# Thermokoppel.net
KiCad netlist of a schematic drawn in Altium Designer
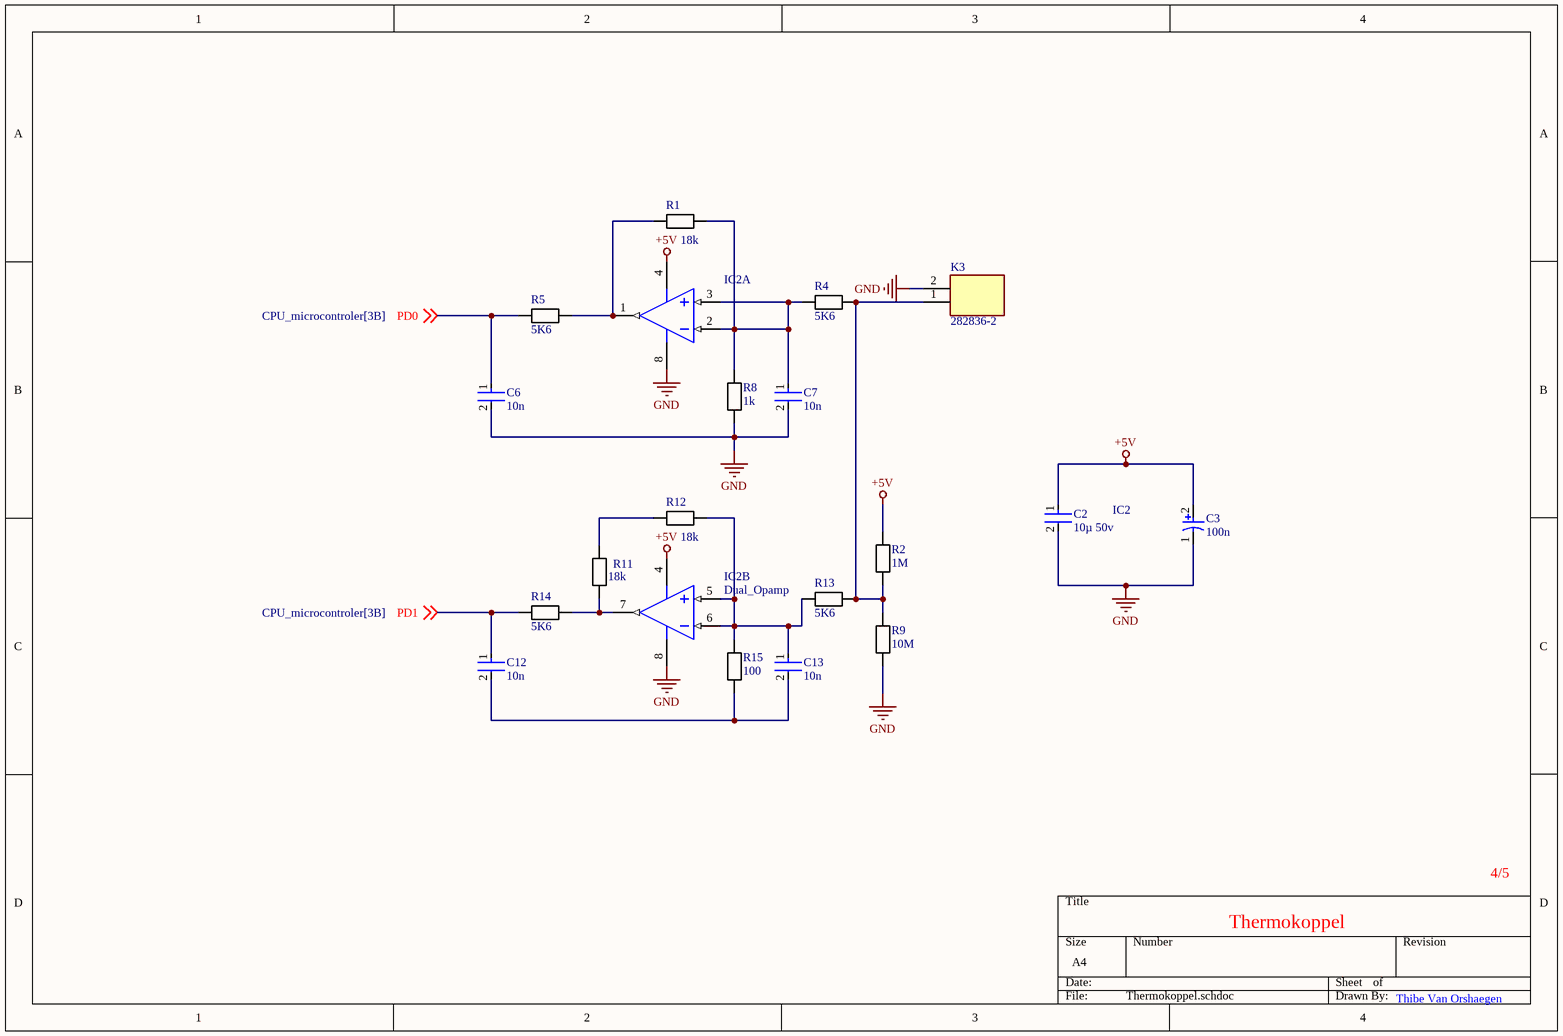
[diagram p0: Thermokoppel.schdoc]

(export (version "E")
  (design (tool "Eeschema 10.0.6"))
  (components
    (comp (ref "C2")
      (value "10µ 50v")
      (footprint "CC_0805_m")
      (fields
        (field (name "MANUFACTURER") "KEMET")
        (field (name "OCTOPART") "https://octopart.com/c0805c224k5ractu-kemet-144670")
        (field (name "MANUFACTURER PART NUMBER") "C0805C224K5RACTU")
      )
      (libsource (lib "Soldeerstation") (part "Capacitor_Ceramic"))
    )
    (comp (ref "C3")
      (value "100n")
      (footprint "CE_D8_L10")
      (fields (field (name "MANUFACTURER") "Panasonic"))
      (libsource (lib "Soldeerstation") (part "Capacitor_Electrolytic"))
    )
    (comp (ref "C6")
      (value "10n")
      (footprint "CC_0805_m")
      (fields
        (field (name "MANUFACTURER") "KEMET")
        (field (name "OCTOPART") "https://octopart.com/c0805c224k5ractu-kemet-144670")
        (field (name "MANUFACTURER PART NUMBER") "C0805C224K5RACTU")
      )
      (libsource (lib "Soldeerstation") (part "Capacitor_Ceramic"))
    )
    (comp (ref "C7")
      (value "10n")
      (footprint "CC_0805_m")
      (fields
        (field (name "MANUFACTURER") "KEMET")
        (field (name "OCTOPART") "https://octopart.com/c0805c224k5ractu-kemet-144670")
        (field (name "MANUFACTURER PART NUMBER") "C0805C224K5RACTU")
      )
      (libsource (lib "Soldeerstation") (part "Capacitor_Ceramic"))
    )
    (comp (ref "C12")
      (value "10n")
      (footprint "CC_0805_m")
      (fields
        (field (name "MANUFACTURER") "KEMET")
        (field (name "OCTOPART") "https://octopart.com/c0805c224k5ractu-kemet-144670")
        (field (name "MANUFACTURER PART NUMBER") "C0805C224K5RACTU")
      )
      (libsource (lib "Soldeerstation") (part "Capacitor_Ceramic"))
    )
    (comp (ref "C13")
      (value "10n")
      (footprint "CC_0805_m")
      (fields
        (field (name "MANUFACTURER") "KEMET")
        (field (name "OCTOPART") "https://octopart.com/c0805c224k5ractu-kemet-144670")
        (field (name "MANUFACTURER PART NUMBER") "C0805C224K5RACTU")
      )
      (libsource (lib "Soldeerstation") (part "Capacitor_Ceramic"))
    )
    (comp (ref "IC2")
      (value "Dual_Opamp")
      (footprint "MSOP_8_M")
      (libsource (lib "Schlib2") (part "Dual_Opamp"))
    )
    (comp (ref "K3")
      (value "282836-2")
      (footprint "PcbLib3:Schroefconnector 2 Pin")
      (description "Connector")
      (libsource (lib "Soldeerstation") (part "Schroefconnector 2 Pin L"))
    )
    (comp (ref "R1")
      (value "18k")
      (footprint "RESC2013X50X30ML20T20")
      (fields (field (name "MANUFACTURER") "Vishay Dale") (field (name "PART NUMBER") "CRCW08050000Z0EA"))
      (libsource (lib "Soldeerstation") (part "Weerstand"))
    )
    (comp (ref "R2")
      (value "1M")
      (footprint "RESC2013X50X30ML20T20")
      (fields (field (name "MANUFACTURER") "Vishay Dale") (field (name "PART NUMBER") "CRCW08050000Z0EA"))
      (libsource (lib "Soldeerstation") (part "Weerstand"))
    )
    (comp (ref "R4")
      (value "5K6")
      (footprint "RESC2013X50X30ML20T20")
      (fields (field (name "MANUFACTURER") "Vishay Dale") (field (name "PART NUMBER") "CRCW08050000Z0EA"))
      (libsource (lib "Soldeerstation") (part "Weerstand"))
    )
    (comp (ref "R5")
      (value "5K6")
      (footprint "RESC2013X50X30ML20T20")
      (fields (field (name "MANUFACTURER") "Vishay Dale") (field (name "PART NUMBER") "CRCW08050000Z0EA"))
      (libsource (lib "Soldeerstation") (part "Weerstand"))
    )
    (comp (ref "R8")
      (value "1k")
      (footprint "RESC2013X50X30ML20T20")
      (fields (field (name "MANUFACTURER") "Vishay Dale") (field (name "PART NUMBER") "CRCW08050000Z0EA"))
      (libsource (lib "Soldeerstation") (part "Weerstand"))
    )
    (comp (ref "R9")
      (value "10M")
      (footprint "RESC2013X50X30ML20T20")
      (fields (field (name "MANUFACTURER") "Vishay Dale") (field (name "PART NUMBER") "CRCW08050000Z0EA"))
      (libsource (lib "Soldeerstation") (part "Weerstand"))
    )
    (comp (ref "R11")
      (value "18k")
      (footprint "RESC2013X50X30ML20T20")
      (fields (field (name "MANUFACTURER") "Vishay Dale") (field (name "PART NUMBER") "CRCW08050000Z0EA"))
      (libsource (lib "Soldeerstation") (part "Weerstand"))
    )
    (comp (ref "R12")
      (value "18k")
      (footprint "RESC2013X50X30ML20T20")
      (fields (field (name "MANUFACTURER") "Vishay Dale") (field (name "PART NUMBER") "CRCW08050000Z0EA"))
      (libsource (lib "Soldeerstation") (part "Weerstand"))
    )
    (comp (ref "R13")
      (value "5K6")
      (footprint "RESC2013X50X30ML20T20")
      (fields (field (name "MANUFACTURER") "Vishay Dale") (field (name "PART NUMBER") "CRCW08050000Z0EA"))
      (libsource (lib "Soldeerstation") (part "Weerstand"))
    )
    (comp (ref "R14")
      (value "5K6")
      (footprint "RESC2013X50X30ML20T20")
      (fields (field (name "MANUFACTURER") "Vishay Dale") (field (name "PART NUMBER") "CRCW08050000Z0EA"))
      (libsource (lib "Soldeerstation") (part "Weerstand"))
    )
    (comp (ref "R15")
      (value "100")
      (footprint "RESC2013X50X30ML20T20")
      (fields (field (name "MANUFACTURER") "Vishay Dale") (field (name "PART NUMBER") "CRCW08050000Z0EA"))
      (libsource (lib "Soldeerstation") (part "Weerstand"))
    )
  )
  (nets
    (net (code "1") (name "+5V") (class "Default")
      (node (ref "C2") (pin "1") (pinfunction "1_1") (pintype "passive"))
      (node (ref "C3") (pin "2") (pinfunction "2_2") (pintype "passive"))
      (node (ref "IC2") (pin "4") (pinfunction "VSS_4") (pintype "power_in"))
      (node (ref "R2") (pin "2") (pinfunction "2_2") (pintype "passive"))
    )
    (net (code "2") (name "GND") (class "Default")
      (node (ref "C2") (pin "2") (pinfunction "2_2") (pintype "passive"))
      (node (ref "C3") (pin "1") (pinfunction "1_1") (pintype "passive"))
      (node (ref "C6") (pin "2") (pinfunction "2_2") (pintype "passive"))
      (node (ref "C7") (pin "2") (pinfunction "2_2") (pintype "passive"))
      (node (ref "IC2") (pin "8") (pinfunction "VDD_8") (pintype "power_in"))
      (node (ref "K3") (pin "2") (pinfunction "2_2") (pintype "passive"))
      (node (ref "R8") (pin "1") (pinfunction "1_1") (pintype "passive"))
      (node (ref "R9") (pin "1") (pinfunction "1_1") (pintype "passive"))
    )
    (net (code "3") (name "Net-(C12-Pad2)") (class "Default")
      (node (ref "C12") (pin "2") (pinfunction "2_2") (pintype "passive"))
      (node (ref "C13") (pin "2") (pinfunction "2_2") (pintype "passive"))
      (node (ref "R15") (pin "1") (pinfunction "1_1") (pintype "passive"))
    )
    (net (code "4") (name "Net-(IC2A-VINA+)") (class "Default")
      (node (ref "C7") (pin "1") (pinfunction "1_1") (pintype "passive"))
      (node (ref "IC2") (pin "2") (pinfunction "VINA-_2") (pintype "input"))
      (node (ref "IC2") (pin "3") (pinfunction "VINA+_3") (pintype "input"))
      (node (ref "R1") (pin "2") (pinfunction "2_2") (pintype "passive"))
      (node (ref "R4") (pin "1") (pinfunction "1_1") (pintype "passive"))
      (node (ref "R8") (pin "2") (pinfunction "2_2") (pintype "passive"))
    )
    (net (code "5") (name "Net-(IC2A-VOUTA)") (class "Default")
      (node (ref "IC2") (pin "1") (pinfunction "VOUTA_1") (pintype "output"))
      (node (ref "R1") (pin "1") (pinfunction "1_1") (pintype "passive"))
      (node (ref "R5") (pin "2") (pinfunction "2_2") (pintype "passive"))
    )
    (net (code "6") (name "Net-(IC2B-VINB+)") (class "Default")
      (node (ref "C13") (pin "1") (pinfunction "1_1") (pintype "passive"))
      (node (ref "IC2") (pin "5") (pinfunction "VINB+_5") (pintype "input"))
      (node (ref "IC2") (pin "6") (pinfunction "VINB-_6") (pintype "input"))
      (node (ref "R12") (pin "2") (pinfunction "2_2") (pintype "passive"))
      (node (ref "R13") (pin "1") (pinfunction "1_1") (pintype "passive"))
      (node (ref "R15") (pin "2") (pinfunction "2_2") (pintype "passive"))
    )
    (net (code "7") (name "Net-(IC2B-VOUTB)") (class "Default")
      (node (ref "IC2") (pin "7") (pinfunction "VOUTB_7") (pintype "output"))
      (node (ref "R11") (pin "1") (pinfunction "1_1") (pintype "passive"))
      (node (ref "R14") (pin "2") (pinfunction "2_2") (pintype "passive"))
    )
    (net (code "8") (name "Net-(K3-Pad1)") (class "Default")
      (node (ref "K3") (pin "1") (pinfunction "1_1") (pintype "passive"))
      (node (ref "R13") (pin "2") (pinfunction "2_2") (pintype "passive"))
      (node (ref "R2") (pin "1") (pinfunction "1_1") (pintype "passive"))
      (node (ref "R4") (pin "2") (pinfunction "2_2") (pintype "passive"))
      (node (ref "R9") (pin "2") (pinfunction "2_2") (pintype "passive"))
    )
    (net (code "9") (name "Net-(R11-Pad2)") (class "Default")
      (node (ref "R11") (pin "2") (pinfunction "2_2") (pintype "passive"))
      (node (ref "R12") (pin "1") (pinfunction "1_1") (pintype "passive"))
    )
    (net (code "10") (name "PD0") (class "Default")
      (node (ref "C6") (pin "1") (pinfunction "1_1") (pintype "passive"))
      (node (ref "R5") (pin "1") (pinfunction "1_1") (pintype "passive"))
    )
    (net (code "11") (name "PD1") (class "Default")
      (node (ref "C12") (pin "1") (pinfunction "1_1") (pintype "passive"))
      (node (ref "R14") (pin "1") (pinfunction "1_1") (pintype "passive"))
    )
  )
)
